# U_I_Meter_DC.net
KiCad netlist of a schematic drawn in Altium Designer
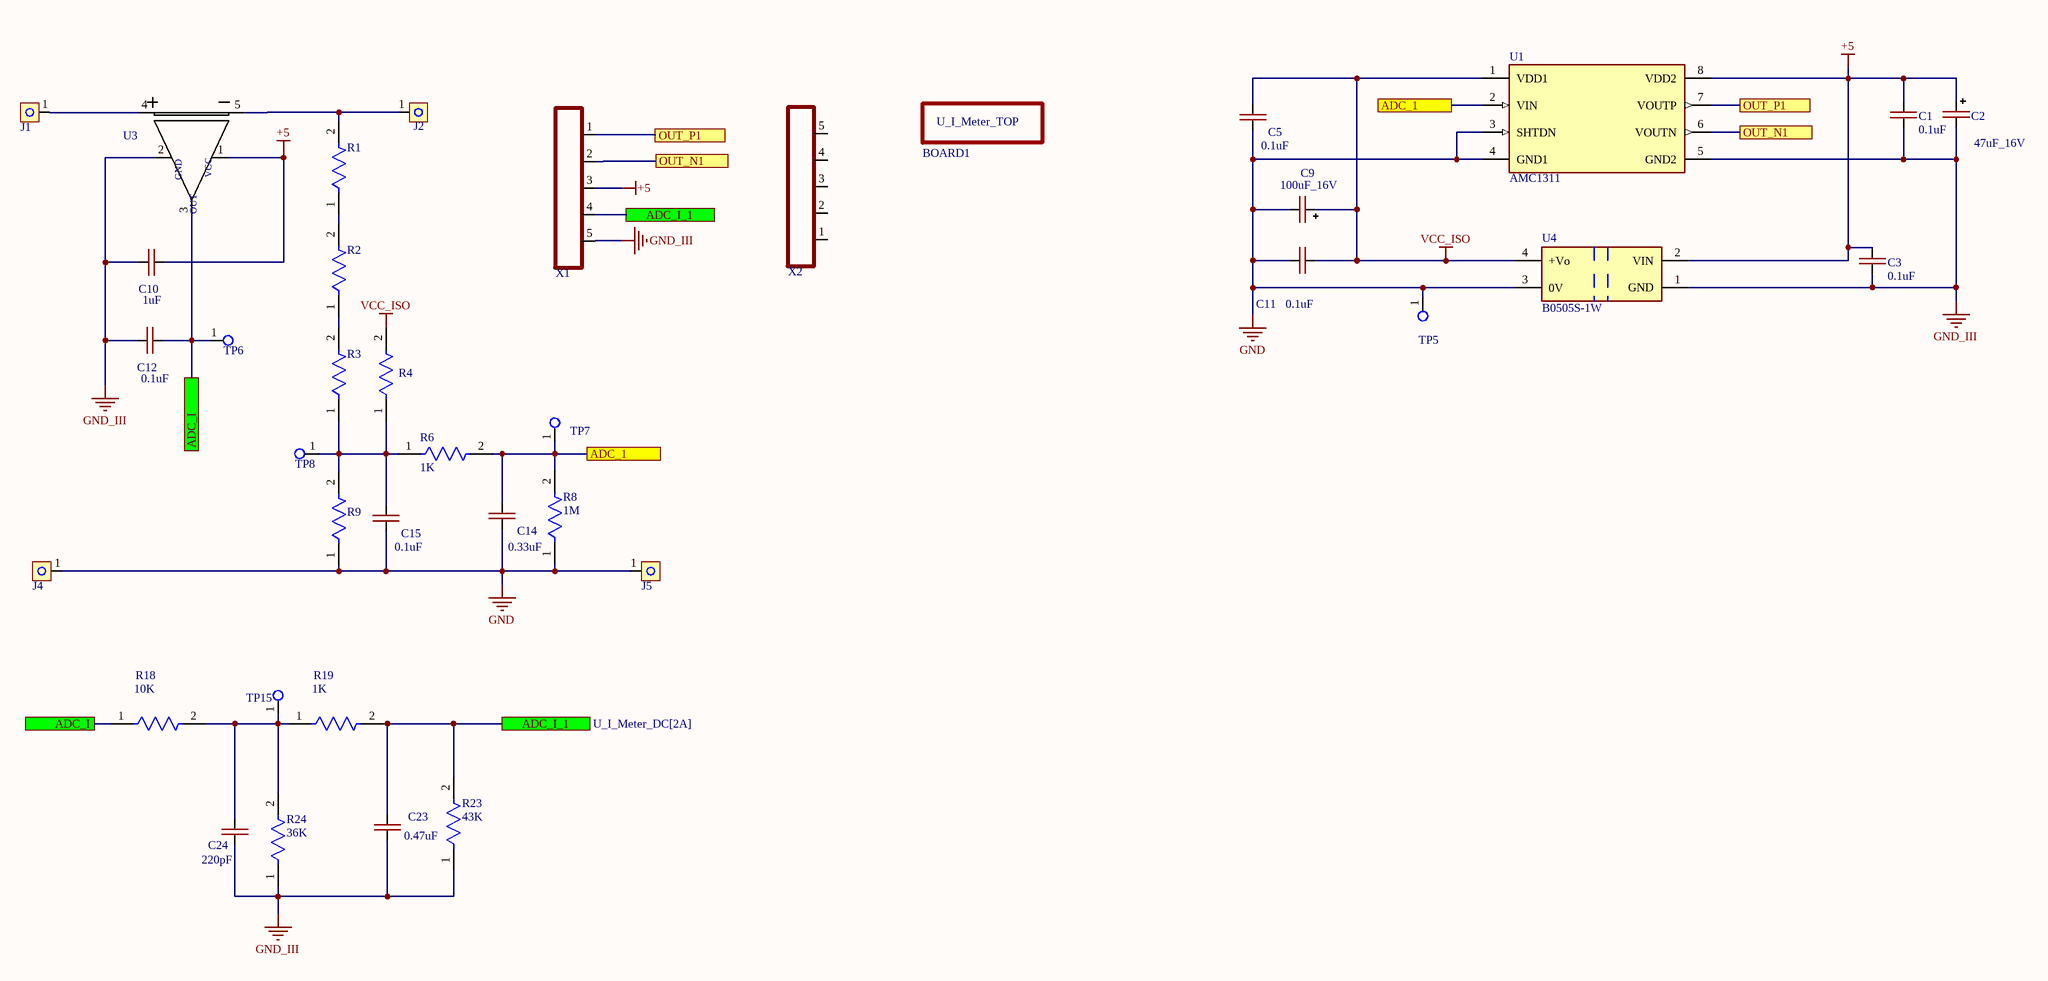
[diagram p0: U_I_Meter_DC.SchDoc]

(export (version "E")
  (design (tool "Eeschema 10.0.6"))
  (components
    (comp (ref "BOARD1")
      (value "U_I_Meter_TOP")
      (footprint "U_I_Meter_TOP")
      (libsource (lib "U_I_Meter_TOP") (part "U_I_Meter_TOP"))
    )
    (comp (ref "C1")
      (value "0.1uF")
      (footprint "CAP-0805")
      (libsource (lib "PASSIVE_COMPONENTS") (part "CAP-NON-POLAR"))
    )
    (comp (ref "C2")
      (value "47uF_16V")
      (footprint "CAP-TAN-D")
      (libsource (lib "PASSIVE_COMPONENTS") (part "CAP-POLAR"))
    )
    (comp (ref "C3")
      (value "0.1uF")
      (footprint "CAP-0805")
      (libsource (lib "PASSIVE_COMPONENTS") (part "CAP-NON-POLAR"))
    )
    (comp (ref "C5")
      (value "0.1uF")
      (footprint "CAP-0805")
      (libsource (lib "PASSIVE_COMPONENTS") (part "CAP-NON-POLAR"))
    )
    (comp (ref "C9")
      (value "100uF_16V")
      (footprint "CAP-TAN-D")
      (libsource (lib "PASSIVE_COMPONENTS") (part "CAP_POL_SMD"))
    )
    (comp (ref "C10")
      (value "1uF")
      (footprint "CAP-0805")
      (libsource (lib "PASSIVE_COMPONENTS") (part "CAP-NON-POLAR"))
    )
    (comp (ref "C11")
      (value "0.1uF")
      (footprint "CAP-0805")
      (libsource (lib "PASSIVE_COMPONENTS") (part "CAP-NON-POLAR"))
    )
    (comp (ref "C12")
      (value "0.1uF")
      (footprint "CAP-0805")
      (libsource (lib "PASSIVE_COMPONENTS") (part "CAP-NON-POLAR"))
    )
    (comp (ref "C14")
      (value "0.33uF")
      (footprint "CAP-0805")
      (libsource (lib "PASSIVE_COMPONENTS") (part "CAP-NON-POLAR"))
    )
    (comp (ref "C15")
      (value "0.1uF")
      (footprint "CAP-0805")
      (libsource (lib "PASSIVE_COMPONENTS") (part "CAP-NON-POLAR"))
    )
    (comp (ref "C23")
      (value "0.47uF")
      (footprint "CAP-0805")
      (libsource (lib "PASSIVE_COMPONENTS") (part "CAP-NON-POLAR"))
    )
    (comp (ref "C24")
      (value "220pF")
      (footprint "CAP-0805")
      (libsource (lib "PASSIVE_COMPONENTS") (part "CAP-NON-POLAR"))
    )
    (comp (ref "J1")
      (value "MG_136_HT")
      (footprint "Conn_MEIGAN_MG136HT")
      (libsource (lib "Connectors") (part "Connector_MEIGAN_MG136HT"))
    )
    (comp (ref "J2")
      (value "MG_136_HT")
      (footprint "Conn_MEIGAN_MG136HT")
      (libsource (lib "") (part "Connector_MEIGAN_MG136HT_1"))
    )
    (comp (ref "J4")
      (value "MG_136_HT")
      (footprint "Conn_MEIGAN_MG136HT")
      (libsource (lib "Connectors") (part "Connector_MEIGAN_MG136HT"))
    )
    (comp (ref "J5")
      (value "MG_136_HT")
      (footprint "Conn_MEIGAN_MG136HT")
      (libsource (lib "") (part "Connector_MEIGAN_MG136HT_1"))
    )
    (comp (ref "R1")
      (value "~")
      (footprint "RES-2512")
      (libsource (lib "PASSIVE_COMPONENTS") (part "RES-CONST"))
    )
    (comp (ref "R2")
      (value "~")
      (footprint "RES-2512")
      (libsource (lib "PASSIVE_COMPONENTS") (part "RES-CONST"))
    )
    (comp (ref "R3")
      (value "~")
      (footprint "RES-2512")
      (libsource (lib "PASSIVE_COMPONENTS") (part "RES-CONST"))
    )
    (comp (ref "R4")
      (value "~")
      (footprint "RES-0805")
      (libsource (lib "PASSIVE_COMPONENTS") (part "RES-CONST"))
    )
    (comp (ref "R6")
      (value "1K")
      (footprint "RES-0805")
      (libsource (lib "PASSIVE_COMPONENTS") (part "RES-CONST"))
    )
    (comp (ref "R8")
      (value "1M")
      (footprint "RES-0805")
      (libsource (lib "PASSIVE_COMPONENTS") (part "RES-CONST"))
    )
    (comp (ref "R9")
      (value "RES_1210")
      (footprint "RES_SMD_1210_IPC_B")
      (libsource (lib "PASSIVE_COMPONENTS") (part "RES_1210"))
    )
    (comp (ref "R18")
      (value "10K")
      (footprint "RES-0805")
      (libsource (lib "PASSIVE_COMPONENTS") (part "RES-CONST"))
    )
    (comp (ref "R19")
      (value "1K")
      (footprint "RES-0805")
      (description "10K")
      (libsource (lib "PASSIVE_COMPONENTS") (part "RES-CONST"))
    )
    (comp (ref "R23")
      (value "43K")
      (footprint "RES-0805")
      (libsource (lib "PASSIVE_COMPONENTS") (part "RES-CONST"))
    )
    (comp (ref "R24")
      (value "36K")
      (footprint "RES-0805")
      (libsource (lib "PASSIVE_COMPONENTS") (part "RES-CONST"))
    )
    (comp (ref "TP5")
      (value "Test_Point_PCB")
      (footprint "Pin_Test_Point(Pink)")
      (description "Test_Point")
      (libsource (lib "Connectors") (part "TP_PCB?"))
    )
    (comp (ref "TP6")
      (value "Test_Point_PCB")
      (footprint "Test_Point")
      (description "Test_Point")
      (libsource (lib "Connectors") (part "TP_PCB?"))
    )
    (comp (ref "TP7")
      (value "Test_Point_PCB")
      (footprint "Test_Point")
      (description "Test_Point")
      (libsource (lib "Connectors") (part "TP_PCB?"))
    )
    (comp (ref "TP8")
      (value "Test_Point_PCB")
      (footprint "Test_Point")
      (description "Test_Point")
      (libsource (lib "Connectors") (part "TP_PCB?"))
    )
    (comp (ref "TP15")
      (value "Test_Point_PCB")
      (footprint "Test_Point")
      (description "Test_Point")
      (libsource (lib "Connectors") (part "TP_PCB?"))
    )
    (comp (ref "U1")
      (value "AMC1311")
      (footprint "FP-DWV0008A-MFG")
      (libsource (lib "Integrated_Circuts") (part "AMC1311"))
    )
    (comp (ref "U3")
      (value "ACS758")
      (footprint "ACS758-100")
      (libsource (lib "Integrated_Circuts") (part "ACS758"))
    )
    (comp (ref "U4")
      (value "B0505S-1W")
      (footprint "B0505S-1W")
      (libsource (lib "Integrated_Circuts") (part "B0505S-1W"))
    )
    (comp (ref "X1")
      (value "CONN-5-PIN")
      (footprint "CONN-PLS-5-2.54mm")
      (libsource (lib "") (part "CONN-5-PIN_1"))
    )
    (comp (ref "X2")
      (value "CONN-5-PIN")
      (footprint "CONN-PLS-5-2.54mm")
      (libsource (lib "PLS-5__") (part "CONN-5-PIN"))
    )
  )
  (nets
    (net (code "1") (name "+5") (class "Default")
      (node (ref "C1") (pin "1") (pinfunction "1_1") (pintype "passive"))
      (node (ref "C10") (pin "2") (pinfunction "2_2") (pintype "passive"))
      (node (ref "C2") (pin "1") (pinfunction "+_1") (pintype "passive"))
      (node (ref "C3") (pin "1") (pinfunction "1_1") (pintype "passive"))
      (node (ref "U1") (pin "8") (pinfunction "VDD2_8") (pintype "power_in"))
      (node (ref "U3") (pin "1") (pinfunction "+VCC_1") (pintype "passive"))
      (node (ref "U4") (pin "2") (pinfunction "VIN_2") (pintype "power_in"))
      (node (ref "X1") (pin "3") (pinfunction "3_3") (pintype "passive"))
    )
    (net (code "2") (name "/ADC_1") (class "Default")
      (node (ref "C14") (pin "2") (pinfunction "2_2") (pintype "passive"))
      (node (ref "R6") (pin "2") (pinfunction "2_2") (pintype "passive"))
      (node (ref "R8") (pin "2") (pinfunction "2_2") (pintype "passive"))
      (node (ref "TP7") (pin "1") (pinfunction "G9_1") (pintype "passive"))
      (node (ref "U1") (pin "2") (pinfunction "VIN_2") (pintype "input"))
    )
    (net (code "3") (name "/ADC_I") (class "Default")
      (node (ref "C12") (pin "2") (pinfunction "2_2") (pintype "passive"))
      (node (ref "R18") (pin "1") (pinfunction "1_1") (pintype "passive"))
      (node (ref "TP6") (pin "1") (pinfunction "G9_1") (pintype "passive"))
      (node (ref "U3") (pin "3") (pinfunction "OUT_3") (pintype "passive"))
    )
    (net (code "4") (name "/ADC_I_1") (class "Default")
      (node (ref "C23") (pin "2") (pinfunction "2_2") (pintype "passive"))
      (node (ref "R19") (pin "2") (pinfunction "2_2") (pintype "passive"))
      (node (ref "R23") (pin "2") (pinfunction "2_2") (pintype "passive"))
      (node (ref "X1") (pin "4") (pinfunction "4_4") (pintype "passive"))
    )
    (net (code "5") (name "/OUT_N1") (class "Default")
      (node (ref "U1") (pin "6") (pinfunction "VOUTN_6") (pintype "output"))
      (node (ref "X1") (pin "2") (pinfunction "2_2") (pintype "passive"))
    )
    (net (code "6") (name "/OUT_P1") (class "Default")
      (node (ref "U1") (pin "7") (pinfunction "VOUTP_7") (pintype "output"))
      (node (ref "X1") (pin "1") (pinfunction "1_1") (pintype "passive"))
    )
    (net (code "7") (name "GND") (class "Default")
      (node (ref "C11") (pin "2") (pinfunction "2_2") (pintype "passive"))
      (node (ref "C14") (pin "1") (pinfunction "1_1") (pintype "passive"))
      (node (ref "C15") (pin "1") (pinfunction "1_1") (pintype "passive"))
      (node (ref "C5") (pin "1") (pinfunction "1_1") (pintype "passive"))
      (node (ref "C9") (pin "2") (pinfunction "-_2") (pintype "passive"))
      (node (ref "J4") (pin "1") (pinfunction "17_1") (pintype "passive"))
      (node (ref "J5") (pin "1") (pinfunction "17_1") (pintype "passive"))
      (node (ref "R8") (pin "1") (pinfunction "1_1") (pintype "passive"))
      (node (ref "R9") (pin "1") (pinfunction "1_1") (pintype "passive"))
      (node (ref "TP5") (pin "1") (pinfunction "G9_1") (pintype "passive"))
      (node (ref "U1") (pin "3") (pinfunction "SHTDN_3") (pintype "input"))
      (node (ref "U1") (pin "4") (pinfunction "GND1_4") (pintype "power_in"))
      (node (ref "U4") (pin "3") (pinfunction "0V_3") (pintype "power_in"))
    )
    (net (code "8") (name "GND_III") (class "Default")
      (node (ref "C1") (pin "2") (pinfunction "2_2") (pintype "passive"))
      (node (ref "C10") (pin "1") (pinfunction "1_1") (pintype "passive"))
      (node (ref "C12") (pin "1") (pinfunction "1_1") (pintype "passive"))
      (node (ref "C2") (pin "2") (pinfunction "-_2") (pintype "passive"))
      (node (ref "C23") (pin "1") (pinfunction "1_1") (pintype "passive"))
      (node (ref "C24") (pin "1") (pinfunction "1_1") (pintype "passive"))
      (node (ref "C3") (pin "2") (pinfunction "2_2") (pintype "passive"))
      (node (ref "R23") (pin "1") (pinfunction "1_1") (pintype "passive"))
      (node (ref "R24") (pin "1") (pinfunction "1_1") (pintype "passive"))
      (node (ref "U1") (pin "5") (pinfunction "GND2_5") (pintype "power_in"))
      (node (ref "U3") (pin "2") (pinfunction "GND_2") (pintype "passive"))
      (node (ref "U4") (pin "1") (pinfunction "GND_1") (pintype "power_in"))
      (node (ref "X1") (pin "5") (pinfunction "5_5") (pintype "passive"))
    )
    (net (code "9") (name "Net-(J1-17)") (class "Default")
      (node (ref "J1") (pin "1") (pinfunction "17_1") (pintype "passive"))
      (node (ref "U3") (pin "4") (pinfunction "+IP_4") (pintype "passive"))
    )
    (net (code "10") (name "Net-(J2-17)") (class "Default")
      (node (ref "J2") (pin "1") (pinfunction "17_1") (pintype "passive"))
      (node (ref "R1") (pin "2") (pinfunction "2_2") (pintype "passive"))
      (node (ref "U3") (pin "5") (pinfunction "-IP_5") (pintype "passive"))
    )
    (net (code "11") (name "Net-(R1-Pad1)") (class "Default")
      (node (ref "R1") (pin "1") (pinfunction "1_1") (pintype "passive"))
      (node (ref "R2") (pin "2") (pinfunction "2_2") (pintype "passive"))
    )
    (net (code "12") (name "Net-(R2-Pad1)") (class "Default")
      (node (ref "R2") (pin "1") (pinfunction "1_1") (pintype "passive"))
      (node (ref "R3") (pin "2") (pinfunction "2_2") (pintype "passive"))
    )
    (net (code "13") (name "Net-(TP8-G9)") (class "Default")
      (node (ref "C15") (pin "2") (pinfunction "2_2") (pintype "passive"))
      (node (ref "R3") (pin "1") (pinfunction "1_1") (pintype "passive"))
      (node (ref "R4") (pin "1") (pinfunction "1_1") (pintype "passive"))
      (node (ref "R6") (pin "1") (pinfunction "1_1") (pintype "passive"))
      (node (ref "R9") (pin "2") (pinfunction "2_2") (pintype "passive"))
      (node (ref "TP8") (pin "1") (pinfunction "G9_1") (pintype "passive"))
    )
    (net (code "14") (name "Net-(TP15-G9)") (class "Default")
      (node (ref "C24") (pin "2") (pinfunction "2_2") (pintype "passive"))
      (node (ref "R18") (pin "2") (pinfunction "2_2") (pintype "passive"))
      (node (ref "R19") (pin "1") (pinfunction "1_1") (pintype "passive"))
      (node (ref "R24") (pin "2") (pinfunction "2_2") (pintype "passive"))
      (node (ref "TP15") (pin "1") (pinfunction "G9_1") (pintype "passive"))
    )
    (net (code "15") (name "VCC_ISO") (class "Default")
      (node (ref "C11") (pin "1") (pinfunction "1_1") (pintype "passive"))
      (node (ref "C5") (pin "2") (pinfunction "2_2") (pintype "passive"))
      (node (ref "C9") (pin "1") (pinfunction "+_1") (pintype "passive"))
      (node (ref "R4") (pin "2") (pinfunction "2_2") (pintype "passive"))
      (node (ref "U1") (pin "1") (pinfunction "VDD1_1") (pintype "power_in"))
      (node (ref "U4") (pin "4") (pinfunction "+Vo_4") (pintype "power_in"))
    )
    (net (code "16") (name "unconnected-(X2-Pad1)") (class "Default")
      (node (ref "X2") (pin "1") (pinfunction "1_1") (pintype "passive"))
    )
    (net (code "17") (name "unconnected-(X2-Pad2)") (class "Default")
      (node (ref "X2") (pin "2") (pinfunction "2_2") (pintype "passive"))
    )
    (net (code "18") (name "unconnected-(X2-Pad3)") (class "Default")
      (node (ref "X2") (pin "3") (pinfunction "3_3") (pintype "passive"))
    )
    (net (code "19") (name "unconnected-(X2-Pad4)") (class "Default")
      (node (ref "X2") (pin "4") (pinfunction "4_4") (pintype "passive"))
    )
    (net (code "20") (name "unconnected-(X2-Pad5)") (class "Default")
      (node (ref "X2") (pin "5") (pinfunction "5_5") (pintype "passive"))
    )
  )
)
